# 12VMPPT_V1_AsBuilt.net
KiCad netlist of a schematic drawn in EAGLE
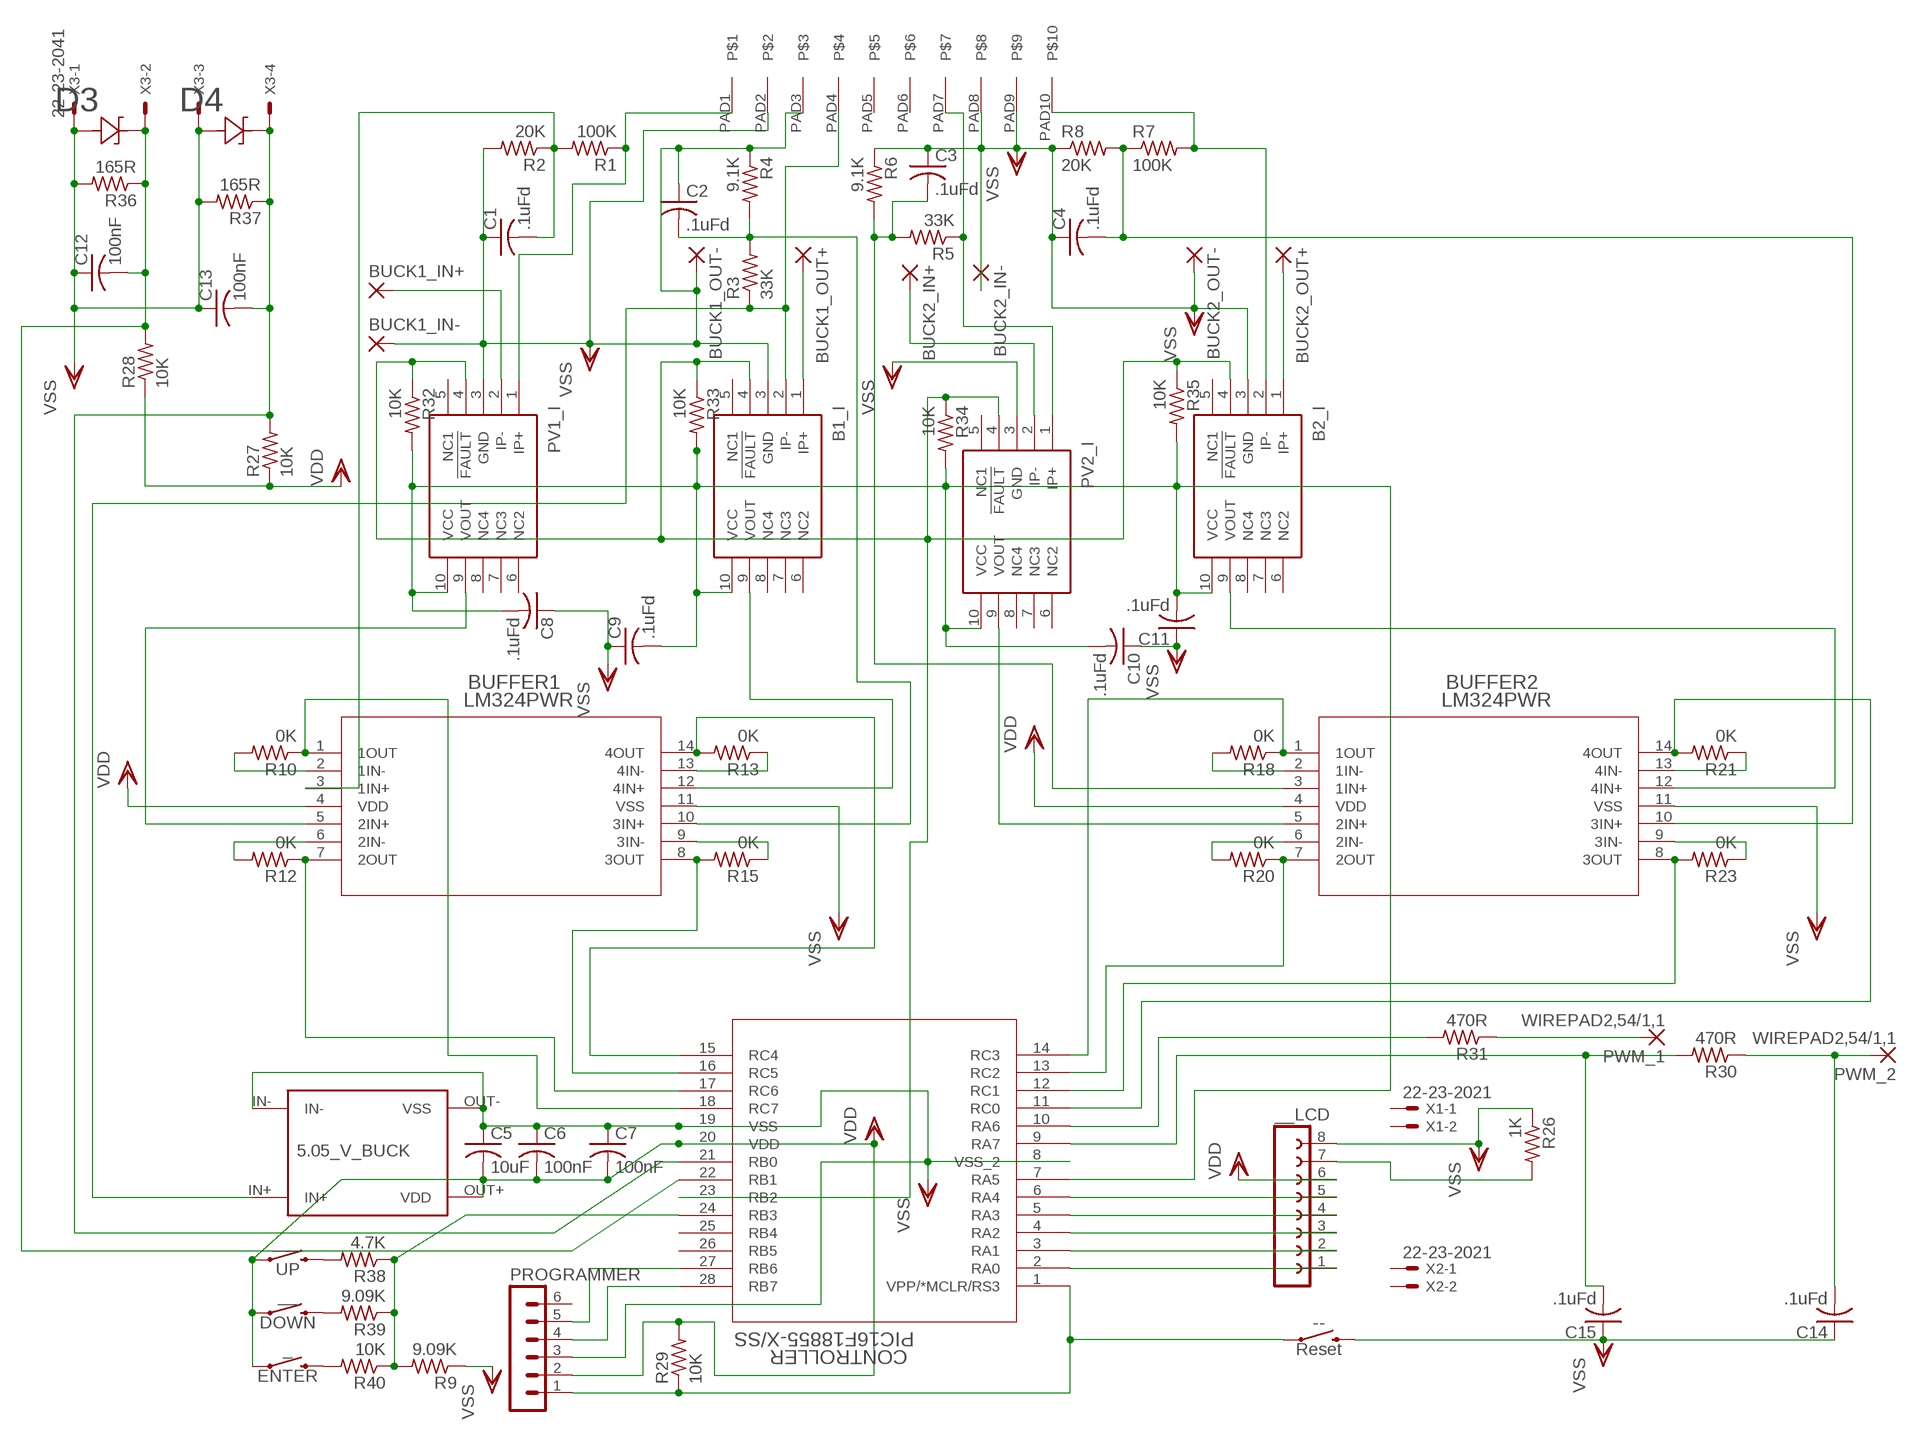
[diagram p0: schematic, sheet 1]

(export (version "E")
  (design (tool "Eeschema 10.0.6"))
  (components
    (comp (ref "--")
      (value "Reset")
      (footprint "eagle-import:TACTILE_SWITCH_PTH_6.0MM")
      (libsource (lib "eagle-import") (part "MOMENTARY-SWITCH-SPST-PTH-6.0MM"))
    )
    (comp (ref "5.05_V_BUCK")
      (value "TINY_BUCK")
      (footprint "eagle-import:TINY_BUCK")
      (libsource (lib "eagle-import") (part "TINY_BUCK"))
    )
    (comp (ref "B1_I")
      (value "ACS711KEXLT-15AB-T")
      (footprint "eagle-import:EX-PACKAGE")
      (libsource (lib "eagle-import") (part "ACS711KEXLT-15AB-T"))
    )
    (comp (ref "B2_I")
      (value "ACS711KEXLT-15AB-T")
      (footprint "eagle-import:EX-PACKAGE")
      (libsource (lib "eagle-import") (part "ACS711KEXLT-15AB-T"))
    )
    (comp (ref "BUCK1_IN+")
      (value "3,81/1,4")
      (footprint "eagle-import:3,81_1,4")
      (libsource (lib "eagle-import") (part "3,81/1,4"))
    )
    (comp (ref "BUCK1_IN-")
      (value "3,81/1,4")
      (footprint "eagle-import:3,81_1,4")
      (libsource (lib "eagle-import") (part "3,81/1,4"))
    )
    (comp (ref "BUCK1_OUT+")
      (value "3,81/1,4")
      (footprint "eagle-import:3,81_1,4")
      (libsource (lib "eagle-import") (part "3,81/1,4"))
    )
    (comp (ref "BUCK1_OUT-")
      (value "3,81/1,4")
      (footprint "eagle-import:3,81_1,4")
      (libsource (lib "eagle-import") (part "3,81/1,4"))
    )
    (comp (ref "BUCK2_IN+")
      (value "3,81/1,4")
      (footprint "eagle-import:3,81_1,4")
      (libsource (lib "eagle-import") (part "3,81/1,4"))
    )
    (comp (ref "BUCK2_IN-")
      (value "3,81/1,4")
      (footprint "eagle-import:3,81_1,4")
      (libsource (lib "eagle-import") (part "3,81/1,4"))
    )
    (comp (ref "BUCK2_OUT+")
      (value "3,81/1,4")
      (footprint "eagle-import:3,81_1,4")
      (libsource (lib "eagle-import") (part "3,81/1,4"))
    )
    (comp (ref "BUCK2_OUT-")
      (value "3,81/1,4")
      (footprint "eagle-import:3,81_1,4")
      (libsource (lib "eagle-import") (part "3,81/1,4"))
    )
    (comp (ref "BUFFER1")
      (value "LM324PWR")
      (footprint "eagle-import:PW14")
      (libsource (lib "eagle-import") (part "LM324PWR"))
    )
    (comp (ref "BUFFER2")
      (value "LM324PWR")
      (footprint "eagle-import:PW14")
      (libsource (lib "eagle-import") (part "LM324PWR"))
    )
    (comp (ref "C1")
      (value ".1uFd")
      (footprint "eagle-import:C0603")
      (libsource (lib "eagle-import") (part "C-USC0603"))
    )
    (comp (ref "C2")
      (value ".1uFd")
      (footprint "eagle-import:C0603")
      (libsource (lib "eagle-import") (part "C-USC0603"))
    )
    (comp (ref "C3")
      (value ".1uFd")
      (footprint "eagle-import:C0603")
      (libsource (lib "eagle-import") (part "C-USC0603"))
    )
    (comp (ref "C4")
      (value ".1uFd")
      (footprint "eagle-import:C0603")
      (libsource (lib "eagle-import") (part "C-USC0603"))
    )
    (comp (ref "C5")
      (value "10uF")
      (footprint "eagle-import:C0603")
      (libsource (lib "eagle-import") (part "C-USC0603"))
    )
    (comp (ref "C6")
      (value "100nF")
      (footprint "eagle-import:C0603")
      (libsource (lib "eagle-import") (part "C-USC0603"))
    )
    (comp (ref "C7")
      (value "100nF")
      (footprint "eagle-import:C0603")
      (libsource (lib "eagle-import") (part "C-USC0603"))
    )
    (comp (ref "C8")
      (value ".1uFd")
      (footprint "eagle-import:C0603")
      (libsource (lib "eagle-import") (part "C-USC0603"))
    )
    (comp (ref "C9")
      (value ".1uFd")
      (footprint "eagle-import:C0603")
      (libsource (lib "eagle-import") (part "C-USC0603"))
    )
    (comp (ref "C10")
      (value ".1uFd")
      (footprint "eagle-import:C0603")
      (libsource (lib "eagle-import") (part "C-USC0603"))
    )
    (comp (ref "C11")
      (value ".1uFd")
      (footprint "eagle-import:C0603")
      (libsource (lib "eagle-import") (part "C-USC0603"))
    )
    (comp (ref "C12")
      (value "100nF")
      (footprint "eagle-import:C0603")
      (libsource (lib "eagle-import") (part "C-USC0603"))
    )
    (comp (ref "C13")
      (value "100nF")
      (footprint "eagle-import:C0603")
      (libsource (lib "eagle-import") (part "C-USC0603"))
    )
    (comp (ref "C14")
      (value ".1uFd")
      (footprint "eagle-import:C0603")
      (libsource (lib "eagle-import") (part "C-USC0603"))
    )
    (comp (ref "C15")
      (value ".1uFd")
      (footprint "eagle-import:C0603")
      (libsource (lib "eagle-import") (part "C-USC0603"))
    )
    (comp (ref "CONTROLLER")
      (value "PIC16F18855-X/SS")
      (footprint "eagle-import:SSOP28_MC")
      (fields
        (field (name "MANUFACTURER_PART_NUMBER") "pic16f18855-x/ss")
        (field (name "COPYRIGHT") "Copyright (C) 2016 Accelerated Designs. All rights reserved")
      )
      (libsource (lib "eagle-import") (part "PIC16F18855-X/SS"))
    )
    (comp (ref "D3")
      (value "CZRU52C3V3")
      (footprint "eagle-import:CZRU")
      (libsource (lib "eagle-import") (part "CZRU52C3V3"))
    )
    (comp (ref "D4")
      (value "CZRU52C3V3")
      (footprint "eagle-import:CZRU")
      (libsource (lib "eagle-import") (part "CZRU52C3V3"))
    )
    (comp (ref "PROGRAMMER")
      (value "MA06-1")
      (footprint "eagle-import:MA06-1")
      (libsource (lib "eagle-import") (part "MA06-1"))
    )
    (comp (ref "PV1_I")
      (value "ACS711KEXLT-15AB-T")
      (footprint "eagle-import:EX-PACKAGE")
      (libsource (lib "eagle-import") (part "ACS711KEXLT-15AB-T"))
    )
    (comp (ref "PV2_I")
      (value "ACS711KEXLT-15AB-T")
      (footprint "eagle-import:EX-PACKAGE")
      (libsource (lib "eagle-import") (part "ACS711KEXLT-15AB-T"))
    )
    (comp (ref "PWM_1")
      (value "WIREPAD2,54/1,1")
      (footprint "eagle-import:2,54_1,1")
      (libsource (lib "eagle-import") (part "WIREPAD2,54/1,1"))
    )
    (comp (ref "PWM_2")
      (value "WIREPAD2,54/1,1")
      (footprint "eagle-import:2,54_1,1")
      (libsource (lib "eagle-import") (part "WIREPAD2,54/1,1"))
    )
    (comp (ref "R1")
      (value "100K")
      (footprint "eagle-import:R0603")
      (libsource (lib "eagle-import") (part "resistor_R-US_R0603"))
    )
    (comp (ref "R2")
      (value "20K")
      (footprint "eagle-import:R0603")
      (libsource (lib "eagle-import") (part "resistor_R-US_R0603"))
    )
    (comp (ref "R3")
      (value "33K")
      (footprint "eagle-import:R0603")
      (libsource (lib "eagle-import") (part "resistor_R-US_R0603"))
    )
    (comp (ref "R4")
      (value "9.1K")
      (footprint "eagle-import:R0603")
      (libsource (lib "eagle-import") (part "resistor_R-US_R0603"))
    )
    (comp (ref "R5")
      (value "33K")
      (footprint "eagle-import:R1206")
      (libsource (lib "eagle-import") (part "resistor_R-US_R1206"))
    )
    (comp (ref "R6")
      (value "9.1K")
      (footprint "eagle-import:R0603")
      (libsource (lib "eagle-import") (part "resistor_R-US_R0603"))
    )
    (comp (ref "R7")
      (value "100K")
      (footprint "eagle-import:R0603")
      (libsource (lib "eagle-import") (part "resistor_R-US_R0603"))
    )
    (comp (ref "R8")
      (value "20K")
      (footprint "eagle-import:R0603")
      (libsource (lib "eagle-import") (part "resistor_R-US_R0603"))
    )
    (comp (ref "R9")
      (value "9.09K")
      (footprint "eagle-import:R0603")
      (libsource (lib "eagle-import") (part "resistor_R-US_R0603"))
    )
    (comp (ref "R10")
      (value "0K")
      (footprint "eagle-import:R0603")
      (libsource (lib "eagle-import") (part "resistor_R-US_R0603"))
    )
    (comp (ref "R12")
      (value "0K")
      (footprint "eagle-import:R0603")
      (libsource (lib "eagle-import") (part "resistor_R-US_R0603"))
    )
    (comp (ref "R13")
      (value "0K")
      (footprint "eagle-import:R0603")
      (libsource (lib "eagle-import") (part "resistor_R-US_R0603"))
    )
    (comp (ref "R15")
      (value "0K")
      (footprint "eagle-import:R0603")
      (libsource (lib "eagle-import") (part "resistor_R-US_R0603"))
    )
    (comp (ref "R18")
      (value "0K")
      (footprint "eagle-import:R0603")
      (libsource (lib "eagle-import") (part "resistor_R-US_R0603"))
    )
    (comp (ref "R20")
      (value "0K")
      (footprint "eagle-import:R0603")
      (libsource (lib "eagle-import") (part "resistor_R-US_R0603"))
    )
    (comp (ref "R21")
      (value "0K")
      (footprint "eagle-import:R0603")
      (libsource (lib "eagle-import") (part "resistor_R-US_R0603"))
    )
    (comp (ref "R23")
      (value "0K")
      (footprint "eagle-import:R0603")
      (libsource (lib "eagle-import") (part "resistor_R-US_R0603"))
    )
    (comp (ref "R26")
      (value "1K")
      (footprint "eagle-import:R0603")
      (libsource (lib "eagle-import") (part "resistor_R-US_R0603"))
    )
    (comp (ref "R27")
      (value "10K")
      (footprint "eagle-import:R1206")
      (libsource (lib "eagle-import") (part "R-US_R1206"))
    )
    (comp (ref "R28")
      (value "10K")
      (footprint "eagle-import:R0603")
      (libsource (lib "eagle-import") (part "resistor_R-US_R0603"))
    )
    (comp (ref "R29")
      (value "10K")
      (footprint "eagle-import:R0603")
      (libsource (lib "eagle-import") (part "resistor_R-US_R0603"))
    )
    (comp (ref "R30")
      (value "470R")
      (footprint "eagle-import:R0603")
      (libsource (lib "eagle-import") (part "resistor_R-US_R0603"))
    )
    (comp (ref "R31")
      (value "470R")
      (footprint "eagle-import:R1206")
      (libsource (lib "eagle-import") (part "resistor_R-US_R1206"))
    )
    (comp (ref "R32")
      (value "10K")
      (footprint "eagle-import:R1206")
      (libsource (lib "eagle-import") (part "resistor_R-US_R1206"))
    )
    (comp (ref "R33")
      (value "10K")
      (footprint "eagle-import:R1206")
      (libsource (lib "eagle-import") (part "resistor_R-US_R1206"))
    )
    (comp (ref "R34")
      (value "10K")
      (footprint "eagle-import:R0603")
      (libsource (lib "eagle-import") (part "resistor_R-US_R0603"))
    )
    (comp (ref "R35")
      (value "10K")
      (footprint "eagle-import:R0603")
      (libsource (lib "eagle-import") (part "resistor_R-US_R0603"))
    )
    (comp (ref "R36")
      (value "165R")
      (footprint "eagle-import:R0603")
      (libsource (lib "eagle-import") (part "resistor_R-US_R0603"))
    )
    (comp (ref "R37")
      (value "165R")
      (footprint "eagle-import:R0603")
      (libsource (lib "eagle-import") (part "resistor_R-US_R0603"))
    )
    (comp (ref "R38")
      (value "4.7K")
      (footprint "eagle-import:R0603")
      (libsource (lib "eagle-import") (part "resistor_R-US_R0603"))
    )
    (comp (ref "R39")
      (value "9.09K")
      (footprint "eagle-import:R0603")
      (libsource (lib "eagle-import") (part "resistor_R-US_R0603"))
    )
    (comp (ref "R40")
      (value "10K")
      (footprint "eagle-import:R0603")
      (libsource (lib "eagle-import") (part "resistor_R-US_R0603"))
    )
    (comp (ref "U$1")
      (value "CONN-KF2EDG-10(5.08)E-BAYPLUGGABLECONNECTORS")
      (footprint "eagle-import:CONN-KF2EDG-10(5.08)")
      (libsource (lib "eagle-import") (part "CONN-KF2EDG-10(5.08)E-BAYPLUGGABLECONNECTORS"))
    )
    (comp (ref "X1")
      (value "22-23-2021")
      (footprint "eagle-import:22-23-2021")
      (fields (field (name "MF") "MOLEX"))
      (libsource (lib "eagle-import") (part "22-23-2021"))
    )
    (comp (ref "X2")
      (value "22-23-2021")
      (footprint "eagle-import:22-23-2021")
      (fields (field (name "MF") "MOLEX"))
      (libsource (lib "eagle-import") (part "22-23-2021"))
    )
    (comp (ref "X3")
      (value "22-23-2041")
      (footprint "eagle-import:22-23-2041")
      (fields (field (name "MF") "MOLEX"))
      (libsource (lib "eagle-import") (part "22-23-2041"))
    )
    (comp (ref "_")
      (value "ENTER")
      (footprint "eagle-import:TACTILE_SWITCH_PTH_6.0MM")
      (libsource (lib "eagle-import") (part "MOMENTARY-SWITCH-SPST-PTH-6.0MM"))
    )
    (comp (ref "__")
      (value "DOWN")
      (footprint "eagle-import:TACTILE_SWITCH_PTH_6.0MM")
      (libsource (lib "eagle-import") (part "MOMENTARY-SWITCH-SPST-PTH-6.0MM"))
    )
    (comp (ref "__LCD")
      (value "FE08-1")
      (footprint "eagle-import:FE08")
      (libsource (lib "eagle-import") (part "FE08-1"))
    )
    (comp (ref "___")
      (value "UP")
      (footprint "eagle-import:TACTILE_SWITCH_PTH_6.0MM")
      (libsource (lib "eagle-import") (part "MOMENTARY-SWITCH-SPST-PTH-6.0MM"))
    )
  )
  (nets
    (net (code "1") (name "Net-(B1_I-IP+)") (class "Default")
      (node (ref "B1_I") (pin "1") (pinfunction "IP+_1") (pintype "bidirectional"))
      (node (ref "BUCK1_OUT+") (pin "1") (pinfunction "P_1") (pintype "passive"))
    )
    (net (code "2") (name "Net-(B1_I-IP-)") (class "Default")
      (node (ref "5.05_V_BUCK") (pin "IN+") (pinfunction "IN+_IN+") (pintype "power_in"))
      (node (ref "B1_I") (pin "2") (pinfunction "IP-_2") (pintype "bidirectional"))
      (node (ref "R3") (pin "1") (pinfunction "1_1") (pintype "passive"))
      (node (ref "U$1") (pin "PAD4") (pinfunction "P$4_PAD4") (pintype "bidirectional"))
    )
    (net (code "3") (name "Net-(B1_I-VCC)") (class "Default")
      (node (ref "B1_I") (pin "10") (pinfunction "VCC_10") (pintype "bidirectional"))
      (node (ref "B2_I") (pin "10") (pinfunction "VCC_10") (pintype "bidirectional"))
      (node (ref "C10") (pin "2") (pinfunction "2_2") (pintype "passive"))
      (node (ref "C11") (pin "2") (pinfunction "2_2") (pintype "passive"))
      (node (ref "C8") (pin "2") (pinfunction "2_2") (pintype "passive"))
      (node (ref "C9") (pin "2") (pinfunction "2_2") (pintype "passive"))
      (node (ref "CONTROLLER") (pin "7") (pinfunction "RA5_7") (pintype "bidirectional"))
      (node (ref "PV1_I") (pin "10") (pinfunction "VCC_10") (pintype "bidirectional"))
      (node (ref "PV2_I") (pin "10") (pinfunction "VCC_10") (pintype "bidirectional"))
      (node (ref "R32") (pin "2") (pinfunction "2_2") (pintype "passive"))
      (node (ref "R33") (pin "2") (pinfunction "2_2") (pintype "passive"))
      (node (ref "R34") (pin "2") (pinfunction "2_2") (pintype "passive"))
      (node (ref "R35") (pin "2") (pinfunction "2_2") (pintype "passive"))
    )
    (net (code "4") (name "Net-(B1_I-VOUT)") (class "Default")
      (node (ref "B1_I") (pin "9") (pinfunction "VOUT_9") (pintype "bidirectional"))
      (node (ref "BUFFER1") (pin "12") (pinfunction "4IN+_12") (pintype "input"))
    )
    (net (code "5") (name "Net-(B1_I-~{FAULT})") (class "Default")
      (node (ref "B1_I") (pin "4") (pinfunction "~{FAULT}_4") (pintype "bidirectional"))
      (node (ref "B2_I") (pin "4") (pinfunction "~{FAULT}_4") (pintype "bidirectional"))
      (node (ref "CONTROLLER") (pin "23") (pinfunction "RB2_23") (pintype "bidirectional"))
      (node (ref "PV1_I") (pin "4") (pinfunction "~{FAULT}_4") (pintype "bidirectional"))
      (node (ref "PV2_I") (pin "4") (pinfunction "~{FAULT}_4") (pintype "bidirectional"))
      (node (ref "R32") (pin "1") (pinfunction "1_1") (pintype "passive"))
      (node (ref "R33") (pin "1") (pinfunction "1_1") (pintype "passive"))
      (node (ref "R34") (pin "1") (pinfunction "1_1") (pintype "passive"))
      (node (ref "R35") (pin "1") (pinfunction "1_1") (pintype "passive"))
    )
    (net (code "6") (name "Net-(B2_I-IP+)") (class "Default")
      (node (ref "B2_I") (pin "1") (pinfunction "IP+_1") (pintype "bidirectional"))
      (node (ref "BUCK2_OUT+") (pin "1") (pinfunction "P_1") (pintype "passive"))
    )
    (net (code "7") (name "Net-(B2_I-IP-)") (class "Default")
      (node (ref "B2_I") (pin "2") (pinfunction "IP-_2") (pintype "bidirectional"))
      (node (ref "R7") (pin "2") (pinfunction "2_2") (pintype "passive"))
      (node (ref "U$1") (pin "PAD10") (pinfunction "P$10_PAD10") (pintype "bidirectional"))
    )
    (net (code "8") (name "Net-(B2_I-VOUT)") (class "Default")
      (node (ref "B2_I") (pin "9") (pinfunction "VOUT_9") (pintype "bidirectional"))
      (node (ref "BUFFER2") (pin "12") (pinfunction "4IN+_12") (pintype "input"))
    )
    (net (code "9") (name "Net-(BUCK1_IN+-P)") (class "Default")
      (node (ref "BUCK1_IN+") (pin "1") (pinfunction "P_1") (pintype "passive"))
      (node (ref "PV1_I") (pin "2") (pinfunction "IP-_2") (pintype "bidirectional"))
    )
    (net (code "10") (name "Net-(BUCK2_IN+-P)") (class "Default")
      (node (ref "BUCK2_IN+") (pin "1") (pinfunction "P_1") (pintype "passive"))
      (node (ref "PV2_I") (pin "2") (pinfunction "IP-_2") (pintype "bidirectional"))
    )
    (net (code "11") (name "Net-(BUFFER1-1IN+)") (class "Default")
      (node (ref "BUFFER1") (pin "3") (pinfunction "1IN+_3") (pintype "input"))
      (node (ref "C1") (pin "2") (pinfunction "2_2") (pintype "passive"))
      (node (ref "R1") (pin "2") (pinfunction "2_2") (pintype "passive"))
      (node (ref "R2") (pin "1") (pinfunction "1_1") (pintype "passive"))
    )
    (net (code "12") (name "Net-(BUFFER1-1IN-)") (class "Default")
      (node (ref "BUFFER1") (pin "2") (pinfunction "1IN-_2") (pintype "input"))
      (node (ref "R10") (pin "2") (pinfunction "2_2") (pintype "passive"))
    )
    (net (code "13") (name "Net-(BUFFER1-1OUT)") (class "Default")
      (node (ref "BUFFER1") (pin "1") (pinfunction "1OUT_1") (pintype "output"))
      (node (ref "CONTROLLER") (pin "18") (pinfunction "RC7_18") (pintype "bidirectional"))
      (node (ref "R10") (pin "1") (pinfunction "1_1") (pintype "passive"))
    )
    (net (code "14") (name "Net-(BUFFER1-2IN+)") (class "Default")
      (node (ref "BUFFER1") (pin "5") (pinfunction "2IN+_5") (pintype "input"))
      (node (ref "PV1_I") (pin "9") (pinfunction "VOUT_9") (pintype "bidirectional"))
    )
    (net (code "15") (name "Net-(BUFFER1-2IN-)") (class "Default")
      (node (ref "BUFFER1") (pin "6") (pinfunction "2IN-_6") (pintype "input"))
      (node (ref "R12") (pin "2") (pinfunction "2_2") (pintype "passive"))
    )
    (net (code "16") (name "Net-(BUFFER1-2OUT)") (class "Default")
      (node (ref "BUFFER1") (pin "7") (pinfunction "2OUT_7") (pintype "output"))
      (node (ref "CONTROLLER") (pin "17") (pinfunction "RC6_17") (pintype "bidirectional"))
      (node (ref "R12") (pin "1") (pinfunction "1_1") (pintype "passive"))
    )
    (net (code "17") (name "Net-(BUFFER1-3IN+)") (class "Default")
      (node (ref "BUFFER1") (pin "10") (pinfunction "3IN+_10") (pintype "input"))
      (node (ref "C2") (pin "2") (pinfunction "2_2") (pintype "passive"))
      (node (ref "R3") (pin "2") (pinfunction "2_2") (pintype "passive"))
      (node (ref "R4") (pin "2") (pinfunction "2_2") (pintype "passive"))
    )
    (net (code "18") (name "Net-(BUFFER1-3IN-)") (class "Default")
      (node (ref "BUFFER1") (pin "9") (pinfunction "3IN-_9") (pintype "input"))
      (node (ref "R15") (pin "1") (pinfunction "1_1") (pintype "passive"))
    )
    (net (code "19") (name "Net-(BUFFER1-3OUT)") (class "Default")
      (node (ref "BUFFER1") (pin "8") (pinfunction "3OUT_8") (pintype "output"))
      (node (ref "CONTROLLER") (pin "16") (pinfunction "RC5_16") (pintype "bidirectional"))
      (node (ref "R15") (pin "2") (pinfunction "2_2") (pintype "passive"))
    )
    (net (code "20") (name "Net-(BUFFER1-4IN-)") (class "Default")
      (node (ref "BUFFER1") (pin "13") (pinfunction "4IN-_13") (pintype "input"))
      (node (ref "R13") (pin "1") (pinfunction "1_1") (pintype "passive"))
    )
    (net (code "21") (name "Net-(BUFFER1-4OUT)") (class "Default")
      (node (ref "BUFFER1") (pin "14") (pinfunction "4OUT_14") (pintype "output"))
      (node (ref "CONTROLLER") (pin "15") (pinfunction "RC4_15") (pintype "bidirectional"))
      (node (ref "R13") (pin "2") (pinfunction "2_2") (pintype "passive"))
    )
    (net (code "22") (name "Net-(BUFFER2-1IN+)") (class "Default")
      (node (ref "BUFFER2") (pin "3") (pinfunction "1IN+_3") (pintype "input"))
      (node (ref "C3") (pin "2") (pinfunction "2_2") (pintype "passive"))
      (node (ref "R5") (pin "2") (pinfunction "2_2") (pintype "passive"))
      (node (ref "R6") (pin "2") (pinfunction "2_2") (pintype "passive"))
    )
    (net (code "23") (name "Net-(BUFFER2-1IN-)") (class "Default")
      (node (ref "BUFFER2") (pin "2") (pinfunction "1IN-_2") (pintype "input"))
      (node (ref "R18") (pin "2") (pinfunction "2_2") (pintype "passive"))
    )
    (net (code "24") (name "Net-(BUFFER2-1OUT)") (class "Default")
      (node (ref "BUFFER2") (pin "1") (pinfunction "1OUT_1") (pintype "output"))
      (node (ref "CONTROLLER") (pin "14") (pinfunction "RC3_14") (pintype "bidirectional"))
      (node (ref "R18") (pin "1") (pinfunction "1_1") (pintype "passive"))
    )
    (net (code "25") (name "Net-(BUFFER2-2IN+)") (class "Default")
      (node (ref "BUFFER2") (pin "5") (pinfunction "2IN+_5") (pintype "input"))
      (node (ref "PV2_I") (pin "9") (pinfunction "VOUT_9") (pintype "bidirectional"))
    )
    (net (code "26") (name "Net-(BUFFER2-2IN-)") (class "Default")
      (node (ref "BUFFER2") (pin "6") (pinfunction "2IN-_6") (pintype "input"))
      (node (ref "R20") (pin "2") (pinfunction "2_2") (pintype "passive"))
    )
    (net (code "27") (name "Net-(BUFFER2-2OUT)") (class "Default")
      (node (ref "BUFFER2") (pin "7") (pinfunction "2OUT_7") (pintype "output"))
      (node (ref "CONTROLLER") (pin "13") (pinfunction "RC2_13") (pintype "bidirectional"))
      (node (ref "R20") (pin "1") (pinfunction "1_1") (pintype "passive"))
    )
    (net (code "28") (name "Net-(BUFFER2-3IN+)") (class "Default")
      (node (ref "BUFFER2") (pin "10") (pinfunction "3IN+_10") (pintype "input"))
      (node (ref "C4") (pin "2") (pinfunction "2_2") (pintype "passive"))
      (node (ref "R7") (pin "1") (pinfunction "1_1") (pintype "passive"))
      (node (ref "R8") (pin "2") (pinfunction "2_2") (pintype "passive"))
    )
    (net (code "29") (name "Net-(BUFFER2-3IN-)") (class "Default")
      (node (ref "BUFFER2") (pin "9") (pinfunction "3IN-_9") (pintype "input"))
      (node (ref "R23") (pin "1") (pinfunction "1_1") (pintype "passive"))
    )
    (net (code "30") (name "Net-(BUFFER2-3OUT)") (class "Default")
      (node (ref "BUFFER2") (pin "8") (pinfunction "3OUT_8") (pintype "output"))
      (node (ref "CONTROLLER") (pin "12") (pinfunction "RC1_12") (pintype "bidirectional"))
      (node (ref "R23") (pin "2") (pinfunction "2_2") (pintype "passive"))
    )
    (net (code "31") (name "Net-(BUFFER2-4IN-)") (class "Default")
      (node (ref "BUFFER2") (pin "13") (pinfunction "4IN-_13") (pintype "input"))
      (node (ref "R21") (pin "1") (pinfunction "1_1") (pintype "passive"))
    )
    (net (code "32") (name "Net-(BUFFER2-4OUT)") (class "Default")
      (node (ref "BUFFER2") (pin "14") (pinfunction "4OUT_14") (pintype "output"))
      (node (ref "CONTROLLER") (pin "11") (pinfunction "RC0_11") (pintype "bidirectional"))
      (node (ref "R21") (pin "2") (pinfunction "2_2") (pintype "passive"))
    )
    (net (code "33") (name "Net-(CONTROLLER-RA0)") (class "Default")
      (node (ref "CONTROLLER") (pin "2") (pinfunction "RA0_2") (pintype "bidirectional"))
      (node (ref "__LCD") (pin "1") (pinfunction "1_1") (pintype "passive"))
    )
    (net (code "34") (name "Net-(CONTROLLER-RA1)") (class "Default")
      (node (ref "CONTROLLER") (pin "3") (pinfunction "RA1_3") (pintype "bidirectional"))
      (node (ref "__LCD") (pin "2") (pinfunction "2_2") (pintype "passive"))
    )
    (net (code "35") (name "Net-(CONTROLLER-RA2)") (class "Default")
      (node (ref "CONTROLLER") (pin "4") (pinfunction "RA2_4") (pintype "bidirectional"))
      (node (ref "__LCD") (pin "3") (pinfunction "3_3") (pintype "passive"))
    )
    (net (code "36") (name "Net-(CONTROLLER-RA3)") (class "Default")
      (node (ref "CONTROLLER") (pin "5") (pinfunction "RA3_5") (pintype "bidirectional"))
      (node (ref "__LCD") (pin "4") (pinfunction "4_4") (pintype "passive"))
    )
    (net (code "37") (name "Net-(CONTROLLER-RA4)") (class "Default")
      (node (ref "CONTROLLER") (pin "6") (pinfunction "RA4_6") (pintype "bidirectional"))
      (node (ref "__LCD") (pin "5") (pinfunction "5_5") (pintype "passive"))
    )
    (net (code "38") (name "Net-(CONTROLLER-RA6)") (class "Default")
      (node (ref "CONTROLLER") (pin "10") (pinfunction "RA6_10") (pintype "bidirectional"))
      (node (ref "R31") (pin "2") (pinfunction "2_2") (pintype "passive"))
    )
    (net (code "39") (name "Net-(CONTROLLER-RA7)") (class "Default")
      (node (ref "C15") (pin "2") (pinfunction "2_2") (pintype "passive"))
      (node (ref "CONTROLLER") (pin "9") (pinfunction "RA7_9") (pintype "bidirectional"))
      (node (ref "R30") (pin "2") (pinfunction "2_2") (pintype "passive"))
    )
    (net (code "40") (name "Net-(CONTROLLER-RB0)") (class "Default")
      (node (ref "C13") (pin "2") (pinfunction "2_2") (pintype "passive"))
      (node (ref "CONTROLLER") (pin "21") (pinfunction "RB0_21") (pintype "bidirectional"))
      (node (ref "D4") (pin "1") (pinfunction "11_1") (pintype "passive"))
      (node (ref "R27") (pin "2") (pinfunction "2_2") (pintype "passive"))
      (node (ref "R37") (pin "1") (pinfunction "1_1") (pintype "passive"))
      (node (ref "X3") (pin "4") (pinfunction "S_4") (pintype "passive"))
    )
    (net (code "41") (name "Net-(CONTROLLER-RB1)") (class "Default")
      (node (ref "C12") (pin "2") (pinfunction "2_2") (pintype "passive"))
      (node (ref "CONTROLLER") (pin "22") (pinfunction "RB1_22") (pintype "bidirectional"))
      (node (ref "D3") (pin "1") (pinfunction "11_1") (pintype "passive"))
      (node (ref "R28") (pin "2") (pinfunction "2_2") (pintype "passive"))
      (node (ref "R36") (pin "1") (pinfunction "1_1") (pintype "passive"))
      (node (ref "X3") (pin "2") (pinfunction "S_2") (pintype "passive"))
    )
    (net (code "42") (name "Net-(CONTROLLER-RB3)") (class "Default")
      (node (ref "CONTROLLER") (pin "24") (pinfunction "RB3_24") (pintype "bidirectional"))
      (node (ref "R38") (pin "1") (pinfunction "1_1") (pintype "passive"))
      (node (ref "R39") (pin "1") (pinfunction "1_1") (pintype "passive"))
      (node (ref "R40") (pin "1") (pinfunction "1_1") (pintype "passive"))
      (node (ref "R9") (pin "2") (pinfunction "2_2") (pintype "passive"))
    )
    (net (code "43") (name "Net-(CONTROLLER-RB6)") (class "Default")
      (node (ref "CONTROLLER") (pin "27") (pinfunction "RB6_27") (pintype "bidirectional"))
      (node (ref "PROGRAMMER") (pin "5") (pinfunction "5_5") (pintype "passive"))
    )
    (net (code "44") (name "Net-(CONTROLLER-RB7)") (class "Default")
      (node (ref "CONTROLLER") (pin "28") (pinfunction "RB7_28") (pintype "bidirectional"))
      (node (ref "PROGRAMMER") (pin "4") (pinfunction "4_4") (pintype "passive"))
    )
    (net (code "45") (name "Net-(CONTROLLER-VPP{slash}*MCLR{slash}RS3)") (class "Default")
      (node (ref "--") (pin "1") (pinfunction "1_1") (pintype "passive"))
      (node (ref "CONTROLLER") (pin "1") (pinfunction "VPP/*MCLR/RS3_1") (pintype "bidirectional"))
      (node (ref "PROGRAMMER") (pin "1") (pinfunction "1_1") (pintype "passive"))
      (node (ref "R29") (pin "1") (pinfunction "1_1") (pintype "passive"))
    )
    (net (code "46") (name "Net-(PV1_I-IP+)") (class "Default")
      (node (ref "PV1_I") (pin "1") (pinfunction "IP+_1") (pintype "bidirectional"))
      (node (ref "R1") (pin "1") (pinfunction "1_1") (pintype "passive"))
      (node (ref "U$1") (pin "PAD1") (pinfunction "P$1_PAD1") (pintype "bidirectional"))
    )
    (net (code "47") (name "Net-(PV2_I-IP+)") (class "Default")
      (node (ref "PV2_I") (pin "1") (pinfunction "IP+_1") (pintype "bidirectional"))
      (node (ref "R5") (pin "1") (pinfunction "1_1") (pintype "passive"))
      (node (ref "U$1") (pin "PAD7") (pinfunction "P$7_PAD7") (pintype "bidirectional"))
    )
    (net (code "48") (name "Net-(PWM_1-P)") (class "Default")
      (node (ref "PWM_1") (pin "1") (pinfunction "P_1") (pintype "passive"))
      (node (ref "R31") (pin "1") (pinfunction "1_1") (pintype "passive"))
    )
    (net (code "49") (name "Net-(PWM_2-P)") (class "Default")
      (node (ref "C14") (pin "2") (pinfunction "2_2") (pintype "passive"))
      (node (ref "PWM_2") (pin "1") (pinfunction "P_1") (pintype "passive"))
      (node (ref "R30") (pin "1") (pinfunction "1_1") (pintype "passive"))
    )
    (net (code "50") (name "Net-(R26-Pad2)") (class "Default")
      (node (ref "R26") (pin "2") (pinfunction "2_2") (pintype "passive"))
      (node (ref "__LCD") (pin "7") (pinfunction "7_7") (pintype "passive"))
    )
    (net (code "51") (name "Net-(_-2)") (class "Default")
      (node (ref "R40") (pin "2") (pinfunction "2_2") (pintype "passive"))
      (node (ref "_") (pin "3") (pinfunction "2_3") (pintype "passive"))
    )
    (net (code "52") (name "Net-(__-2)") (class "Default")
      (node (ref "R39") (pin "2") (pinfunction "2_2") (pintype "passive"))
      (node (ref "__") (pin "3") (pinfunction "2_3") (pintype "passive"))
    )
    (net (code "53") (name "Net-(___-2)") (class "Default")
      (node (ref "R38") (pin "2") (pinfunction "2_2") (pintype "passive"))
      (node (ref "___") (pin "3") (pinfunction "2_3") (pintype "passive"))
    )
    (net (code "54") (name "VDD") (class "Default")
      (node (ref "5.05_V_BUCK") (pin "OUT+") (pinfunction "VDD_OUT+") (pintype "power_in"))
      (node (ref "BUFFER1") (pin "4") (pinfunction "VDD_4") (pintype "power_in"))
      (node (ref "BUFFER2") (pin "4") (pinfunction "VDD_4") (pintype "power_in"))
      (node (ref "C5") (pin "2") (pinfunction "2_2") (pintype "passive"))
      (node (ref "C6") (pin "2") (pinfunction "2_2") (pintype "passive"))
      (node (ref "C7") (pin "2") (pinfunction "2_2") (pintype "passive"))
      (node (ref "CONTROLLER") (pin "20") (pinfunction "VDD_20") (pintype "power_in"))
      (node (ref "PROGRAMMER") (pin "2") (pinfunction "2_2") (pintype "passive"))
      (node (ref "R27") (pin "1") (pinfunction "1_1") (pintype "passive"))
      (node (ref "R28") (pin "1") (pinfunction "1_1") (pintype "passive"))
      (node (ref "R29") (pin "2") (pinfunction "2_2") (pintype "passive"))
      (node (ref "_") (pin "1") (pinfunction "1_1") (pintype "passive"))
      (node (ref "__") (pin "1") (pinfunction "1_1") (pintype "passive"))
      (node (ref "__LCD") (pin "6") (pinfunction "6_6") (pintype "passive"))
      (node (ref "___") (pin "1") (pinfunction "1_1") (pintype "passive"))
    )
    (net (code "55") (name "VSS") (class "Default")
      (node (ref "--") (pin "3") (pinfunction "2_3") (pintype "passive"))
      (node (ref "5.05_V_BUCK") (pin "IN-") (pinfunction "IN-_IN-") (pintype "power_in"))
      (node (ref "5.05_V_BUCK") (pin "OUT-") (pinfunction "VSS_OUT-") (pintype "power_in"))
      (node (ref "B1_I") (pin "3") (pinfunction "GND_3") (pintype "bidirectional"))
      (node (ref "B2_I") (pin "3") (pinfunction "GND_3") (pintype "bidirectional"))
      (node (ref "BUCK1_IN-") (pin "1") (pinfunction "P_1") (pintype "passive"))
      (node (ref "BUCK1_OUT-") (pin "1") (pinfunction "P_1") (pintype "passive"))
      (node (ref "BUCK2_IN-") (pin "1") (pinfunction "P_1") (pintype "passive"))
      (node (ref "BUCK2_OUT-") (pin "1") (pinfunction "P_1") (pintype "passive"))
      (node (ref "BUFFER1") (pin "11") (pinfunction "VSS_11") (pintype "power_in"))
      (node (ref "BUFFER2") (pin "11") (pinfunction "VSS_11") (pintype "power_in"))
      (node (ref "C1") (pin "1") (pinfunction "1_1") (pintype "passive"))
      (node (ref "C10") (pin "1") (pinfunction "1_1") (pintype "passive"))
      (node (ref "C11") (pin "1") (pinfunction "1_1") (pintype "passive"))
      (node (ref "C12") (pin "1") (pinfunction "1_1") (pintype "passive"))
      (node (ref "C13") (pin "1") (pinfunction "1_1") (pintype "passive"))
      (node (ref "C14") (pin "1") (pinfunction "1_1") (pintype "passive"))
      (node (ref "C15") (pin "1") (pinfunction "1_1") (pintype "passive"))
      (node (ref "C2") (pin "1") (pinfunction "1_1") (pintype "passive"))
      (node (ref "C3") (pin "1") (pinfunction "1_1") (pintype "passive"))
      (node (ref "C4") (pin "1") (pinfunction "1_1") (pintype "passive"))
      (node (ref "C5") (pin "1") (pinfunction "1_1") (pintype "passive"))
      (node (ref "C6") (pin "1") (pinfunction "1_1") (pintype "passive"))
      (node (ref "C7") (pin "1") (pinfunction "1_1") (pintype "passive"))
      (node (ref "C8") (pin "1") (pinfunction "1_1") (pintype "passive"))
      (node (ref "C9") (pin "1") (pinfunction "1_1") (pintype "passive"))
      (node (ref "CONTROLLER") (pin "19") (pinfunction "VSS_19") (pintype "power_in"))
      (node (ref "CONTROLLER") (pin "8") (pinfunction "VSS_2_8") (pintype "power_in"))
      (node (ref "D3") (pin "2") (pinfunction "22_2") (pintype "passive"))
      (node (ref "D4") (pin "2") (pinfunction "22_2") (pintype "passive"))
      (node (ref "PROGRAMMER") (pin "3") (pinfunction "3_3") (pintype "passive"))
      (node (ref "PV1_I") (pin "3") (pinfunction "GND_3") (pintype "bidirectional"))
      (node (ref "PV2_I") (pin "3") (pinfunction "GND_3") (pintype "bidirectional"))
      (node (ref "R2") (pin "2") (pinfunction "2_2") (pintype "passive"))
      (node (ref "R26") (pin "1") (pinfunction "1_1") (pintype "passive"))
      (node (ref "R36") (pin "2") (pinfunction "2_2") (pintype "passive"))
      (node (ref "R37") (pin "2") (pinfunction "2_2") (pintype "passive"))
      (node (ref "R4") (pin "1") (pinfunction "1_1") (pintype "passive"))
      (node (ref "R6") (pin "1") (pinfunction "1_1") (pintype "passive"))
      (node (ref "R8") (pin "1") (pinfunction "1_1") (pintype "passive"))
      (node (ref "R9") (pin "1") (pinfunction "1_1") (pintype "passive"))
      (node (ref "U$1") (pin "PAD2") (pinfunction "P$2_PAD2") (pintype "bidirectional"))
      (node (ref "U$1") (pin "PAD3") (pinfunction "P$3_PAD3") (pintype "bidirectional"))
      (node (ref "U$1") (pin "PAD8") (pinfunction "P$8_PAD8") (pintype "bidirectional"))
      (node (ref "U$1") (pin "PAD9") (pinfunction "P$9_PAD9") (pintype "bidirectional"))
      (node (ref "X3") (pin "1") (pinfunction "S_1") (pintype "passive"))
      (node (ref "X3") (pin "3") (pinfunction "S_3") (pintype "passive"))
      (node (ref "__LCD") (pin "8") (pinfunction "8_8") (pintype "passive"))
    )
    (net (code "56") (name "unconnected-(B1_I-NC1-Pad5)") (class "Default")
      (node (ref "B1_I") (pin "5") (pinfunction "NC1_5") (pintype "bidirectional"))
    )
    (net (code "57") (name "unconnected-(B1_I-NC2-Pad6)") (class "Default")
      (node (ref "B1_I") (pin "6") (pinfunction "NC2_6") (pintype "bidirectional"))
    )
    (net (code "58") (name "unconnected-(B1_I-NC3-Pad7)") (class "Default")
      (node (ref "B1_I") (pin "7") (pinfunction "NC3_7") (pintype "bidirectional"))
    )
    (net (code "59") (name "unconnected-(B1_I-NC4-Pad8)") (class "Default")
      (node (ref "B1_I") (pin "8") (pinfunction "NC4_8") (pintype "bidirectional"))
    )
    (net (code "60") (name "unconnected-(B2_I-NC1-Pad5)") (class "Default")
      (node (ref "B2_I") (pin "5") (pinfunction "NC1_5") (pintype "bidirectional"))
    )
    (net (code "61") (name "unconnected-(B2_I-NC2-Pad6)") (class "Default")
      (node (ref "B2_I") (pin "6") (pinfunction "NC2_6") (pintype "bidirectional"))
    )
    (net (code "62") (name "unconnected-(B2_I-NC3-Pad7)") (class "Default")
      (node (ref "B2_I") (pin "7") (pinfunction "NC3_7") (pintype "bidirectional"))
    )
    (net (code "63") (name "unconnected-(B2_I-NC4-Pad8)") (class "Default")
      (node (ref "B2_I") (pin "8") (pinfunction "NC4_8") (pintype "bidirectional"))
    )
    (net (code "64") (name "unconnected-(CONTROLLER-RB4-Pad25)") (class "Default")
      (node (ref "CONTROLLER") (pin "25") (pinfunction "RB4_25") (pintype "bidirectional"))
    )
    (net (code "65") (name "unconnected-(CONTROLLER-RB5-Pad26)") (class "Default")
      (node (ref "CONTROLLER") (pin "26") (pinfunction "RB5_26") (pintype "bidirectional"))
    )
    (net (code "66") (name "unconnected-(PROGRAMMER-Pad6)") (class "Default")
      (node (ref "PROGRAMMER") (pin "6") (pinfunction "6_6") (pintype "passive"))
    )
    (net (code "67") (name "unconnected-(PV1_I-NC1-Pad5)") (class "Default")
      (node (ref "PV1_I") (pin "5") (pinfunction "NC1_5") (pintype "bidirectional"))
    )
    (net (code "68") (name "unconnected-(PV1_I-NC2-Pad6)") (class "Default")
      (node (ref "PV1_I") (pin "6") (pinfunction "NC2_6") (pintype "bidirectional"))
    )
    (net (code "69") (name "unconnected-(PV1_I-NC3-Pad7)") (class "Default")
      (node (ref "PV1_I") (pin "7") (pinfunction "NC3_7") (pintype "bidirectional"))
    )
    (net (code "70") (name "unconnected-(PV1_I-NC4-Pad8)") (class "Default")
      (node (ref "PV1_I") (pin "8") (pinfunction "NC4_8") (pintype "bidirectional"))
    )
    (net (code "71") (name "unconnected-(PV2_I-NC1-Pad5)") (class "Default")
      (node (ref "PV2_I") (pin "5") (pinfunction "NC1_5") (pintype "bidirectional"))
    )
    (net (code "72") (name "unconnected-(PV2_I-NC2-Pad6)") (class "Default")
      (node (ref "PV2_I") (pin "6") (pinfunction "NC2_6") (pintype "bidirectional"))
    )
    (net (code "73") (name "unconnected-(PV2_I-NC3-Pad7)") (class "Default")
      (node (ref "PV2_I") (pin "7") (pinfunction "NC3_7") (pintype "bidirectional"))
    )
    (net (code "74") (name "unconnected-(PV2_I-NC4-Pad8)") (class "Default")
      (node (ref "PV2_I") (pin "8") (pinfunction "NC4_8") (pintype "bidirectional"))
    )
    (net (code "75") (name "unconnected-(U$1-P$5-PadPAD5)") (class "Default")
      (node (ref "U$1") (pin "PAD5") (pinfunction "P$5_PAD5") (pintype "bidirectional"))
    )
    (net (code "76") (name "unconnected-(U$1-P$6-PadPAD6)") (class "Default")
      (node (ref "U$1") (pin "PAD6") (pinfunction "P$6_PAD6") (pintype "bidirectional"))
    )
    (net (code "77") (name "unconnected-(X1A-S-Pad1)") (class "Default")
      (node (ref "X1") (pin "1") (pinfunction "S_1") (pintype "passive"))
    )
    (net (code "78") (name "unconnected-(X1B-S-Pad2)") (class "Default")
      (node (ref "X1") (pin "2") (pinfunction "S_2") (pintype "passive"))
    )
    (net (code "79") (name "unconnected-(X2A-S-Pad1)") (class "Default")
      (node (ref "X2") (pin "1") (pinfunction "S_1") (pintype "passive"))
    )
    (net (code "80") (name "unconnected-(X2B-S-Pad2)") (class "Default")
      (node (ref "X2") (pin "2") (pinfunction "S_2") (pintype "passive"))
    )
  )
)
